# IF.net
KiCad netlist of a schematic drawn in Altium Designer
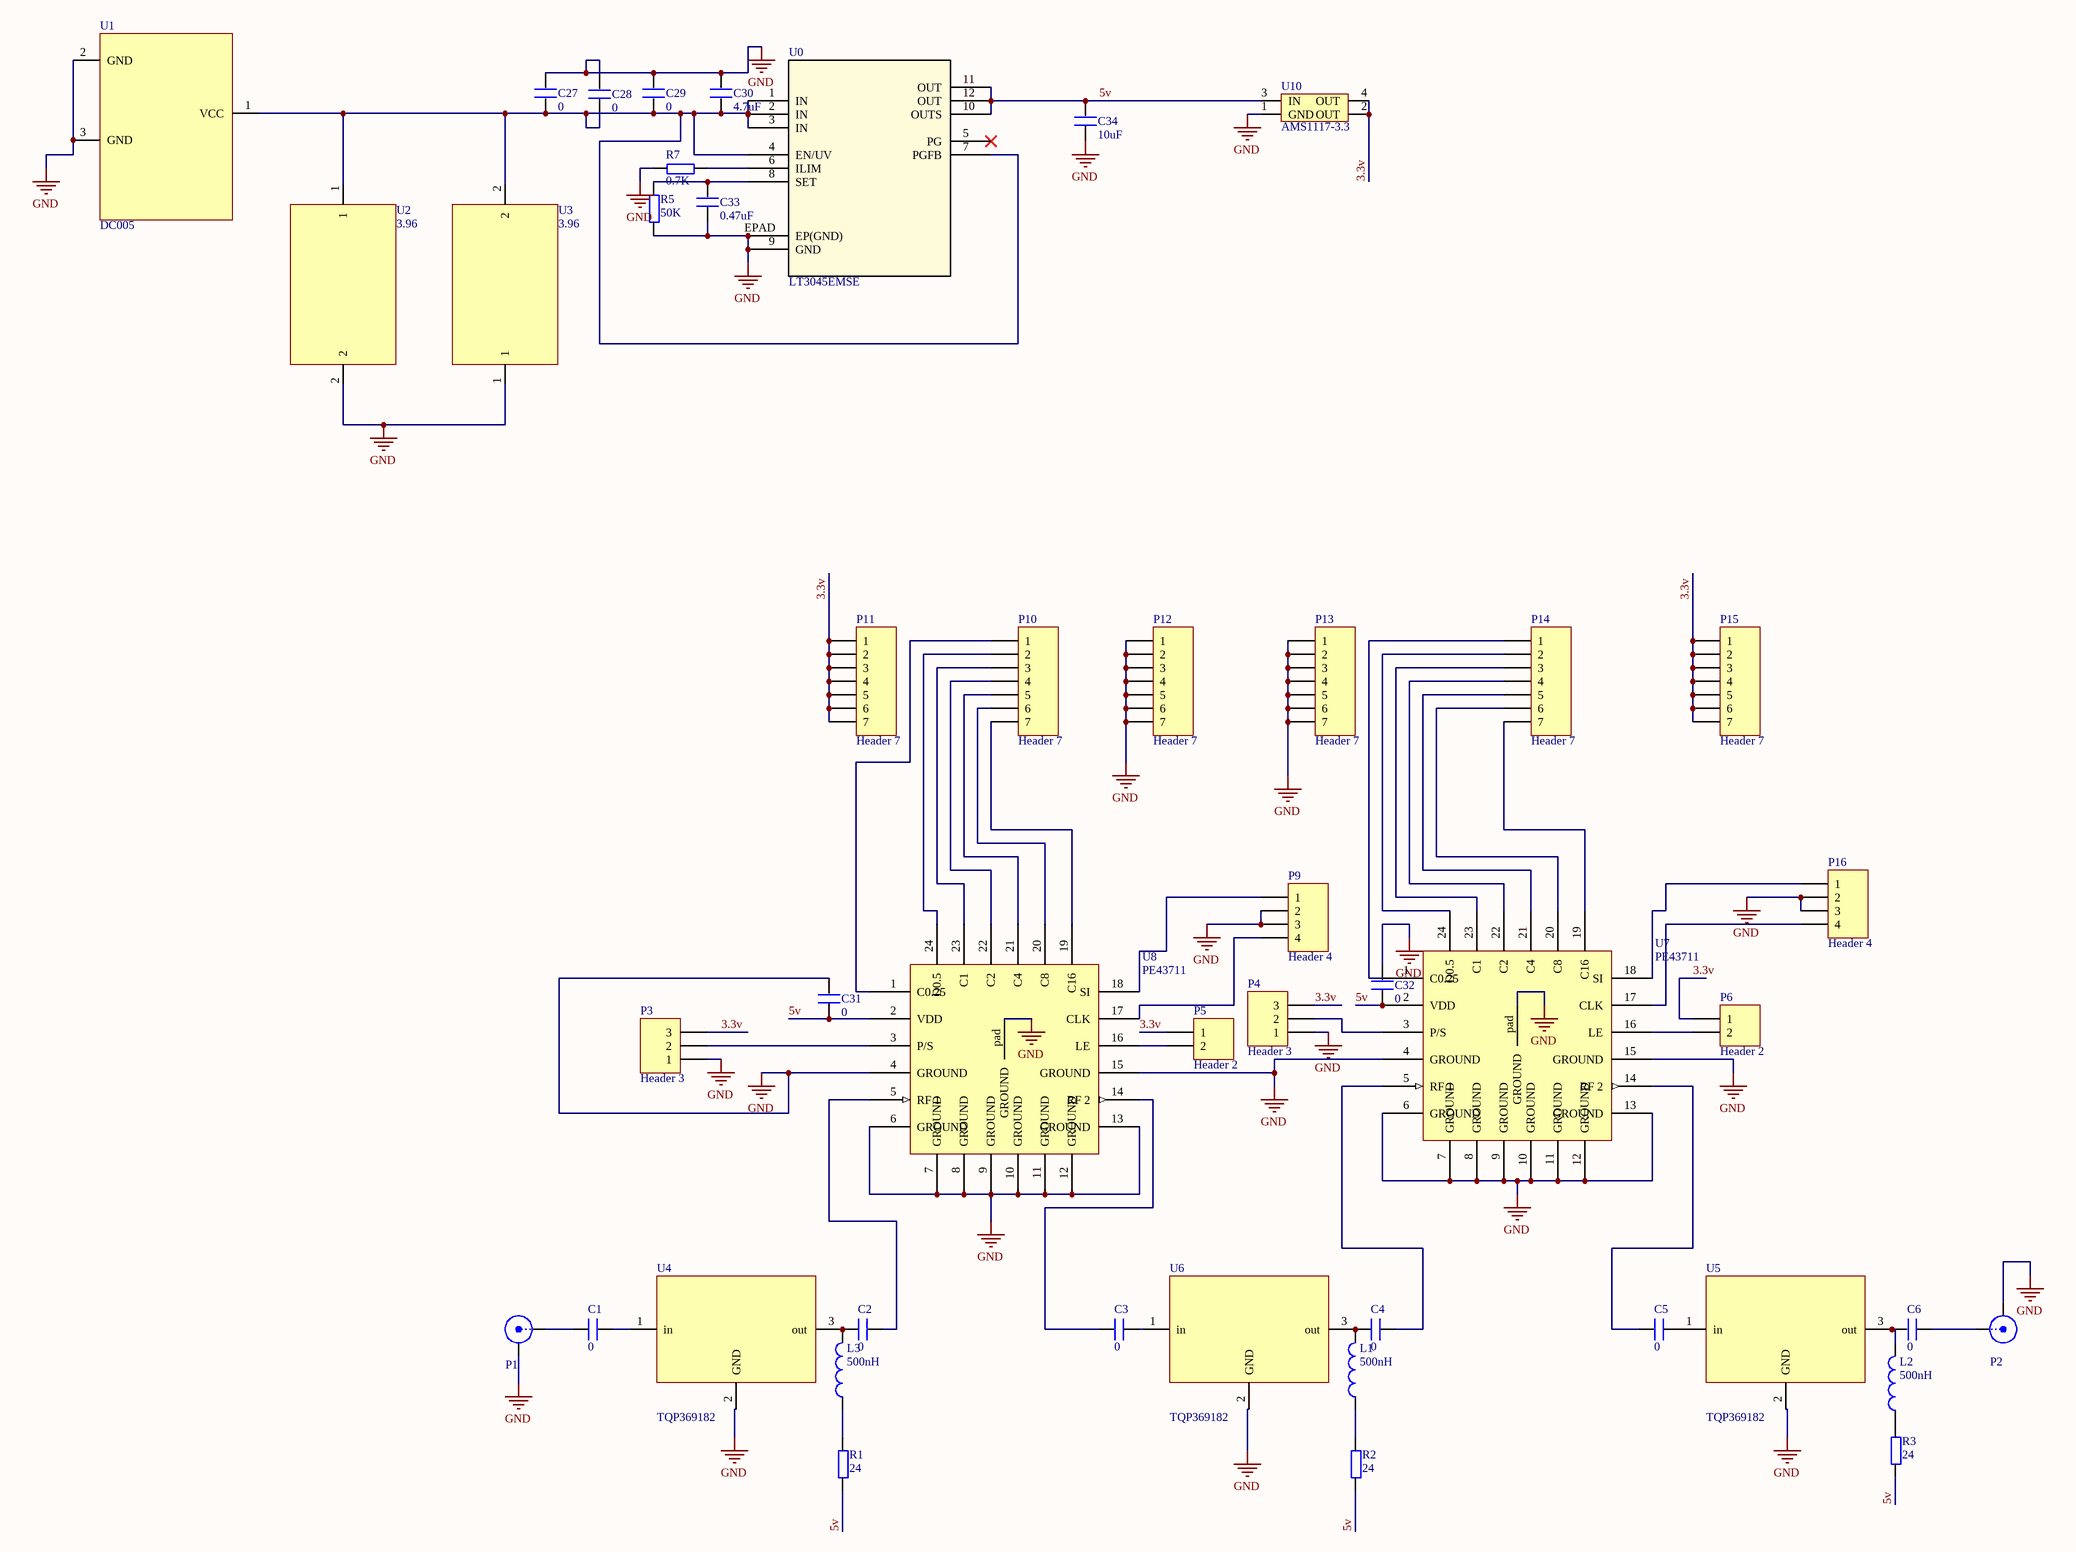
[diagram p0: IF.SchDoc]

(export (version "E")
  (design (tool "Eeschema 10.0.6"))
  (components
    (comp (ref "C1")
      (value "0")
      (footprint "0402")
      (description "Capacitor")
      (libsource (lib "MYLIB") (part "C"))
    )
    (comp (ref "C2")
      (value "0")
      (footprint "0402")
      (description "Capacitor")
      (libsource (lib "MYLIB") (part "C"))
    )
    (comp (ref "C3")
      (value "0")
      (footprint "0402")
      (description "Capacitor")
      (libsource (lib "MYLIB") (part "C"))
    )
    (comp (ref "C4")
      (value "0")
      (footprint "0402")
      (description "Capacitor")
      (libsource (lib "MYLIB") (part "C"))
    )
    (comp (ref "C5")
      (value "0")
      (footprint "0402")
      (description "Capacitor")
      (libsource (lib "MYLIB") (part "C"))
    )
    (comp (ref "C6")
      (value "0")
      (footprint "0402")
      (description "Capacitor")
      (libsource (lib "MYLIB") (part "C"))
    )
    (comp (ref "C27")
      (value "0")
      (footprint "CAP 1.5*4*8")
      (description "Capacitor")
      (libsource (lib "MYLIB") (part "C"))
    )
    (comp (ref "C28")
      (value "0")
      (footprint "CAP 1.5*4*8")
      (description "Capacitor")
      (libsource (lib "MYLIB") (part "C"))
    )
    (comp (ref "C29")
      (value "0")
      (footprint "0603C")
      (description "Capacitor")
      (libsource (lib "MYLIB") (part "C"))
    )
    (comp (ref "C30")
      (value "4.7uF")
      (footprint "0603C")
      (description "Capacitor")
      (libsource (lib "MYLIB") (part "C"))
    )
    (comp (ref "C31")
      (value "0")
      (footprint "0402")
      (description "Capacitor")
      (libsource (lib "MYLIB") (part "C"))
    )
    (comp (ref "C32")
      (value "0")
      (footprint "0402")
      (description "Capacitor")
      (libsource (lib "MYLIB") (part "C"))
    )
    (comp (ref "C33")
      (value "0.47uF")
      (footprint "0402")
      (description "Capacitor")
      (libsource (lib "MYLIB") (part "C"))
    )
    (comp (ref "C34")
      (value "10uF")
      (footprint "0402")
      (description "Capacitor")
      (libsource (lib "MYLIB") (part "C"))
    )
    (comp (ref "L1")
      (value "500nH")
      (footprint "0402")
      (description "Inductor")
      (fields (field (name "PUBLISHER") "Altium Limited"))
      (libsource (lib "MYLIB") (part "Inductor"))
    )
    (comp (ref "L2")
      (value "500nH")
      (footprint "0402")
      (description "Inductor")
      (fields (field (name "PUBLISHER") "Altium Limited"))
      (libsource (lib "MYLIB") (part "Inductor"))
    )
    (comp (ref "L3")
      (value "500nH")
      (footprint "0402")
      (description "Inductor")
      (fields (field (name "PUBLISHER") "Altium Limited"))
      (libsource (lib "MYLIB") (part "Inductor"))
    )
    (comp (ref "P1")
      (value "SMA")
      (footprint "SMA")
      (description "SMA Connector")
      (libsource (lib "MYLIB") (part "SMA"))
    )
    (comp (ref "P2")
      (value "SMA")
      (footprint "SMA")
      (description "SMA Connector")
      (libsource (lib "MYLIB") (part "SMA"))
    )
    (comp (ref "P3")
      (value "Header 3")
      (footprint "HDR1X3")
      (description "Header, 3-Pin")
      (fields (field (name "PUBLISHER") "Altium Limited"))
      (libsource (lib "Miscellaneous Connectors") (part "Header 3"))
    )
    (comp (ref "P4")
      (value "Header 3")
      (footprint "HDR1X3")
      (description "Header, 3-Pin")
      (fields (field (name "PUBLISHER") "Altium Limited"))
      (libsource (lib "Miscellaneous Connectors") (part "Header 3"))
    )
    (comp (ref "P5")
      (value "Header 2")
      (footprint "HDR1X2")
      (description "Header, 2-Pin")
      (fields (field (name "PUBLISHER") "Altium Limited"))
      (libsource (lib "Miscellaneous Connectors") (part "Header 2"))
    )
    (comp (ref "P6")
      (value "Header 2")
      (footprint "HDR1X2")
      (description "Header, 2-Pin")
      (fields (field (name "PUBLISHER") "Altium Limited"))
      (libsource (lib "Miscellaneous Connectors") (part "Header 2"))
    )
    (comp (ref "P9")
      (value "Header 4")
      (footprint "HDR1X4")
      (description "Header, 4-Pin")
      (fields (field (name "PUBLISHER") "Altium Limited"))
      (libsource (lib "Miscellaneous Connectors") (part "Header 4"))
    )
    (comp (ref "P10")
      (value "Header 7")
      (footprint "HDR1X7")
      (description "Header, 7-Pin")
      (fields (field (name "PUBLISHER") "Altium Limited"))
      (libsource (lib "Miscellaneous Connectors") (part "Header 7"))
    )
    (comp (ref "P11")
      (value "Header 7")
      (footprint "HDR1X7")
      (description "Header, 7-Pin")
      (fields (field (name "PUBLISHER") "Altium Limited"))
      (libsource (lib "Miscellaneous Connectors") (part "Header 7"))
    )
    (comp (ref "P12")
      (value "Header 7")
      (footprint "HDR1X7")
      (description "Header, 7-Pin")
      (fields (field (name "PUBLISHER") "Altium Limited"))
      (libsource (lib "Miscellaneous Connectors") (part "Header 7"))
    )
    (comp (ref "P13")
      (value "Header 7")
      (footprint "HDR1X7")
      (description "Header, 7-Pin")
      (fields (field (name "PUBLISHER") "Altium Limited"))
      (libsource (lib "Miscellaneous Connectors") (part "Header 7"))
    )
    (comp (ref "P14")
      (value "Header 7")
      (footprint "HDR1X7")
      (description "Header, 7-Pin")
      (fields (field (name "PUBLISHER") "Altium Limited"))
      (libsource (lib "Miscellaneous Connectors") (part "Header 7"))
    )
    (comp (ref "P15")
      (value "Header 7")
      (footprint "HDR1X7")
      (description "Header, 7-Pin")
      (fields (field (name "PUBLISHER") "Altium Limited"))
      (libsource (lib "Miscellaneous Connectors") (part "Header 7"))
    )
    (comp (ref "P16")
      (value "Header 4")
      (footprint "HDR1X4")
      (description "Header, 4-Pin")
      (fields (field (name "PUBLISHER") "Altium Limited"))
      (libsource (lib "Miscellaneous Connectors") (part "Header 4"))
    )
    (comp (ref "R1")
      (value "24")
      (footprint "0805")
      (description "Resistor")
      (libsource (lib "MYLIB") (part "Resistor"))
    )
    (comp (ref "R2")
      (value "24")
      (footprint "0805")
      (description "Resistor")
      (libsource (lib "MYLIB") (part "Resistor"))
    )
    (comp (ref "R3")
      (value "24")
      (footprint "0805")
      (description "Resistor")
      (libsource (lib "MYLIB") (part "Resistor"))
    )
    (comp (ref "R5")
      (value "50K")
      (footprint "0402")
      (description "Resistor")
      (libsource (lib "MYLIB") (part "Resistor"))
    )
    (comp (ref "R7")
      (value "0.7K")
      (footprint "0402")
      (description "Resistor")
      (libsource (lib "MYLIB") (part "Resistor"))
    )
    (comp (ref "U0")
      (value "LT3045EMSE")
      (footprint "MSOP12-MSE-RevG_ADI")
      (description "No Description Available")
      (fields (field (name "COPYRIGHT") "Copyright (C) 2018 Accelerated Designs. All rights reserved"))
      (libsource (lib "MYLIB") (part "LT3045EMSE"))
    )
    (comp (ref "U1") (value "DC005") (footprint "DC10B") (libsource (lib "MYLIB") (part "DC005")))
    (comp (ref "U2") (value "3.96") (footprint "3.96") (libsource (lib "MYLIB") (part "3.96")))
    (comp (ref "U3") (value "3.96") (footprint "3.96") (libsource (lib "") (part "3.96_1")))
    (comp (ref "U4") (value "TQP369182") (footprint "SOT89_M") (libsource (lib "MYLIB") (part "TQP369182")))
    (comp (ref "U5") (value "TQP369182") (footprint "SOT89_M") (libsource (lib "MYLIB") (part "TQP369182")))
    (comp (ref "U6") (value "TQP369182") (footprint "SOT89_M") (libsource (lib "MYLIB") (part "TQP369182")))
    (comp (ref "U7") (value "PE43711") (footprint "PE43711") (libsource (lib "MYLIB") (part "PE43711")))
    (comp (ref "U8") (value "PE43711") (footprint "PE43711") (libsource (lib "MYLIB") (part "PE43711")))
    (comp (ref "U10") (value "AMS1117-3.3") (footprint "AMS1117") (libsource (lib "MYLIB") (part "AMS1117")))
  )
  (nets
    (net (code "1") (name "/3.3v") (class "Default")
      (node (ref "P11") (pin "1") (pinfunction "1_1") (pintype "passive"))
      (node (ref "P11") (pin "2") (pinfunction "2_2") (pintype "passive"))
      (node (ref "P11") (pin "3") (pinfunction "3_3") (pintype "passive"))
      (node (ref "P11") (pin "4") (pinfunction "4_4") (pintype "passive"))
      (node (ref "P11") (pin "5") (pinfunction "5_5") (pintype "passive"))
      (node (ref "P11") (pin "6") (pinfunction "6_6") (pintype "passive"))
      (node (ref "P11") (pin "7") (pinfunction "7_7") (pintype "passive"))
      (node (ref "P15") (pin "1") (pinfunction "1_1") (pintype "passive"))
      (node (ref "P15") (pin "2") (pinfunction "2_2") (pintype "passive"))
      (node (ref "P15") (pin "3") (pinfunction "3_3") (pintype "passive"))
      (node (ref "P15") (pin "4") (pinfunction "4_4") (pintype "passive"))
      (node (ref "P15") (pin "5") (pinfunction "5_5") (pintype "passive"))
      (node (ref "P15") (pin "6") (pinfunction "6_6") (pintype "passive"))
      (node (ref "P15") (pin "7") (pinfunction "7_7") (pintype "passive"))
      (node (ref "P3") (pin "3") (pinfunction "3_3") (pintype "passive"))
      (node (ref "P4") (pin "3") (pinfunction "3_3") (pintype "passive"))
      (node (ref "P5") (pin "1") (pinfunction "1_1") (pintype "passive"))
      (node (ref "P6") (pin "1") (pinfunction "1_1") (pintype "passive"))
      (node (ref "U10") (pin "2") (pinfunction "OUT_2") (pintype "passive"))
      (node (ref "U10") (pin "4") (pinfunction "OUT_4") (pintype "passive"))
    )
    (net (code "2") (name "/5v") (class "Default")
      (node (ref "C31") (pin "1") (pintype "passive"))
      (node (ref "C32") (pin "1") (pintype "passive"))
      (node (ref "C34") (pin "2") (pintype "passive"))
      (node (ref "R1") (pin "1") (pintype "passive"))
      (node (ref "R2") (pin "1") (pintype "passive"))
      (node (ref "R3") (pin "1") (pintype "passive"))
      (node (ref "U0") (pin "10") (pinfunction "OUTS_10") (pintype "passive"))
      (node (ref "U0") (pin "11") (pinfunction "OUT_11") (pintype "passive"))
      (node (ref "U0") (pin "12") (pinfunction "OUT_12") (pintype "passive"))
      (node (ref "U10") (pin "3") (pinfunction "IN_3") (pintype "passive"))
      (node (ref "U7") (pin "2") (pinfunction "VDD_2") (pintype "power_in"))
      (node (ref "U8") (pin "2") (pinfunction "VDD_2") (pintype "power_in"))
    )
    (net (code "3") (name "GND") (class "Default")
      (node (ref "C27") (pin "2") (pintype "passive"))
      (node (ref "C28") (pin "2") (pintype "passive"))
      (node (ref "C29") (pin "2") (pintype "passive"))
      (node (ref "C30") (pin "2") (pintype "passive"))
      (node (ref "C31") (pin "2") (pintype "passive"))
      (node (ref "C32") (pin "2") (pintype "passive"))
      (node (ref "C33") (pin "1") (pintype "passive"))
      (node (ref "C34") (pin "1") (pintype "passive"))
      (node (ref "P1") (pin "2") (pinfunction "Y_2") (pintype "passive"))
      (node (ref "P12") (pin "1") (pinfunction "1_1") (pintype "passive"))
      (node (ref "P12") (pin "2") (pinfunction "2_2") (pintype "passive"))
      (node (ref "P12") (pin "3") (pinfunction "3_3") (pintype "passive"))
      (node (ref "P12") (pin "4") (pinfunction "4_4") (pintype "passive"))
      (node (ref "P12") (pin "5") (pinfunction "5_5") (pintype "passive"))
      (node (ref "P12") (pin "6") (pinfunction "6_6") (pintype "passive"))
      (node (ref "P12") (pin "7") (pinfunction "7_7") (pintype "passive"))
      (node (ref "P13") (pin "1") (pinfunction "1_1") (pintype "passive"))
      (node (ref "P13") (pin "2") (pinfunction "2_2") (pintype "passive"))
      (node (ref "P13") (pin "3") (pinfunction "3_3") (pintype "passive"))
      (node (ref "P13") (pin "4") (pinfunction "4_4") (pintype "passive"))
      (node (ref "P13") (pin "5") (pinfunction "5_5") (pintype "passive"))
      (node (ref "P13") (pin "6") (pinfunction "6_6") (pintype "passive"))
      (node (ref "P13") (pin "7") (pinfunction "7_7") (pintype "passive"))
      (node (ref "P16") (pin "2") (pinfunction "2_2") (pintype "passive"))
      (node (ref "P16") (pin "3") (pinfunction "3_3") (pintype "passive"))
      (node (ref "P2") (pin "2") (pinfunction "Y_2") (pintype "passive"))
      (node (ref "P3") (pin "1") (pinfunction "1_1") (pintype "passive"))
      (node (ref "P4") (pin "1") (pinfunction "1_1") (pintype "passive"))
      (node (ref "P9") (pin "2") (pinfunction "2_2") (pintype "passive"))
      (node (ref "P9") (pin "3") (pinfunction "3_3") (pintype "passive"))
      (node (ref "R5") (pin "1") (pintype "passive"))
      (node (ref "R7") (pin "1") (pintype "passive"))
      (node (ref "U0") (pin "9") (pinfunction "GND_9") (pintype "passive"))
      (node (ref "U0") (pin "EPAD") (pinfunction "EP(GND)_EPAD") (pintype "passive"))
      (node (ref "U1") (pin "2") (pinfunction "GND_2") (pintype "passive"))
      (node (ref "U1") (pin "3") (pinfunction "GND_3") (pintype "passive"))
      (node (ref "U10") (pin "1") (pinfunction "GND_1") (pintype "passive"))
      (node (ref "U2") (pin "2") (pinfunction "2_2") (pintype "passive"))
      (node (ref "U3") (pin "1") (pinfunction "1_1") (pintype "passive"))
      (node (ref "U4") (pin "2") (pinfunction "GND_2") (pintype "passive"))
      (node (ref "U5") (pin "2") (pinfunction "GND_2") (pintype "passive"))
      (node (ref "U6") (pin "2") (pinfunction "GND_2") (pintype "passive"))
      (node (ref "U7") (pin "10") (pinfunction "GROUND_10") (pintype "passive"))
      (node (ref "U7") (pin "11") (pinfunction "GROUND_11") (pintype "passive"))
      (node (ref "U7") (pin "12") (pinfunction "GROUND_12") (pintype "passive"))
      (node (ref "U7") (pin "13") (pinfunction "GROUND_13") (pintype "passive"))
      (node (ref "U7") (pin "15") (pinfunction "GROUND_15") (pintype "passive"))
      (node (ref "U7") (pin "4") (pinfunction "GROUND_4") (pintype "passive"))
      (node (ref "U7") (pin "6") (pinfunction "GROUND_6") (pintype "passive"))
      (node (ref "U7") (pin "7") (pinfunction "GROUND_7") (pintype "passive"))
      (node (ref "U7") (pin "8") (pinfunction "GROUND_8") (pintype "passive"))
      (node (ref "U7") (pin "9") (pinfunction "GROUND_9") (pintype "passive"))
      (node (ref "U7") (pin "pad") (pinfunction "GROUND_pad") (pintype "passive"))
      (node (ref "U8") (pin "10") (pinfunction "GROUND_10") (pintype "passive"))
      (node (ref "U8") (pin "11") (pinfunction "GROUND_11") (pintype "passive"))
      (node (ref "U8") (pin "12") (pinfunction "GROUND_12") (pintype "passive"))
      (node (ref "U8") (pin "13") (pinfunction "GROUND_13") (pintype "passive"))
      (node (ref "U8") (pin "15") (pinfunction "GROUND_15") (pintype "passive"))
      (node (ref "U8") (pin "4") (pinfunction "GROUND_4") (pintype "passive"))
      (node (ref "U8") (pin "6") (pinfunction "GROUND_6") (pintype "passive"))
      (node (ref "U8") (pin "7") (pinfunction "GROUND_7") (pintype "passive"))
      (node (ref "U8") (pin "8") (pinfunction "GROUND_8") (pintype "passive"))
      (node (ref "U8") (pin "9") (pinfunction "GROUND_9") (pintype "passive"))
      (node (ref "U8") (pin "pad") (pinfunction "GROUND_pad") (pintype "passive"))
    )
    (net (code "4") (name "Net-(L1-Pad1)") (class "Default")
      (node (ref "L1") (pin "1") (pinfunction "1_1") (pintype "passive"))
      (node (ref "R2") (pin "2") (pintype "passive"))
    )
    (net (code "5") (name "Net-(L2-Pad1)") (class "Default")
      (node (ref "L2") (pin "1") (pinfunction "1_1") (pintype "passive"))
      (node (ref "R3") (pin "2") (pintype "passive"))
    )
    (net (code "6") (name "Net-(L3-Pad1)") (class "Default")
      (node (ref "L3") (pin "1") (pinfunction "1_1") (pintype "passive"))
      (node (ref "R1") (pin "2") (pintype "passive"))
    )
    (net (code "7") (name "Net-(P1-X)") (class "Default")
      (node (ref "C1") (pin "1") (pintype "passive"))
      (node (ref "P1") (pin "1") (pinfunction "X_1") (pintype "passive"))
    )
    (net (code "8") (name "Net-(P2-X)") (class "Default")
      (node (ref "C6") (pin "2") (pintype "passive"))
      (node (ref "P2") (pin "1") (pinfunction "X_1") (pintype "passive"))
    )
    (net (code "9") (name "Net-(U0-EN{slash}UV)") (class "Default")
      (node (ref "C27") (pin "1") (pintype "passive"))
      (node (ref "C28") (pin "1") (pintype "passive"))
      (node (ref "C29") (pin "1") (pintype "passive"))
      (node (ref "C30") (pin "1") (pintype "passive"))
      (node (ref "U0") (pin "1") (pinfunction "IN_1") (pintype "passive"))
      (node (ref "U0") (pin "2") (pinfunction "IN_2") (pintype "passive"))
      (node (ref "U0") (pin "3") (pinfunction "IN_3") (pintype "passive"))
      (node (ref "U0") (pin "4") (pinfunction "EN/UV_4") (pintype "passive"))
      (node (ref "U0") (pin "7") (pinfunction "PGFB_7") (pintype "passive"))
      (node (ref "U1") (pin "1") (pinfunction "VCC_1") (pintype "passive"))
      (node (ref "U2") (pin "1") (pinfunction "1_1") (pintype "passive"))
      (node (ref "U3") (pin "2") (pinfunction "2_2") (pintype "passive"))
    )
    (net (code "10") (name "Net-(U0-ILIM)") (class "Default")
      (node (ref "R7") (pin "2") (pintype "passive"))
      (node (ref "U0") (pin "6") (pinfunction "ILIM_6") (pintype "passive"))
    )
    (net (code "11") (name "Net-(U0-SET)") (class "Default")
      (node (ref "C33") (pin "2") (pintype "passive"))
      (node (ref "R5") (pin "2") (pintype "passive"))
      (node (ref "U0") (pin "8") (pinfunction "SET_8") (pintype "passive"))
    )
    (net (code "12") (name "Net-(U4-in)") (class "Default")
      (node (ref "C1") (pin "2") (pintype "passive"))
      (node (ref "U4") (pin "1") (pinfunction "in_1") (pintype "passive"))
    )
    (net (code "13") (name "Net-(U4-out)") (class "Default")
      (node (ref "C2") (pin "1") (pintype "passive"))
      (node (ref "L3") (pin "2") (pinfunction "2_2") (pintype "passive"))
      (node (ref "U4") (pin "3") (pinfunction "out_3") (pintype "passive"))
    )
    (net (code "14") (name "Net-(U5-in)") (class "Default")
      (node (ref "C5") (pin "2") (pintype "passive"))
      (node (ref "U5") (pin "1") (pinfunction "in_1") (pintype "passive"))
    )
    (net (code "15") (name "Net-(U5-out)") (class "Default")
      (node (ref "C6") (pin "1") (pintype "passive"))
      (node (ref "L2") (pin "2") (pinfunction "2_2") (pintype "passive"))
      (node (ref "U5") (pin "3") (pinfunction "out_3") (pintype "passive"))
    )
    (net (code "16") (name "Net-(U6-in)") (class "Default")
      (node (ref "C3") (pin "2") (pintype "passive"))
      (node (ref "U6") (pin "1") (pinfunction "in_1") (pintype "passive"))
    )
    (net (code "17") (name "Net-(U6-out)") (class "Default")
      (node (ref "C4") (pin "1") (pintype "passive"))
      (node (ref "L1") (pin "2") (pinfunction "2_2") (pintype "passive"))
      (node (ref "U6") (pin "3") (pinfunction "out_3") (pintype "passive"))
    )
    (net (code "18") (name "Net-(U7-C0.25)") (class "Default")
      (node (ref "P14") (pin "1") (pinfunction "1_1") (pintype "passive"))
      (node (ref "U7") (pin "1") (pinfunction "C0.25_1") (pintype "open_collector"))
    )
    (net (code "19") (name "Net-(U7-C1)") (class "Default")
      (node (ref "P14") (pin "3") (pinfunction "3_3") (pintype "passive"))
      (node (ref "U7") (pin "23") (pinfunction "C1_23") (pintype "passive"))
    )
    (net (code "20") (name "Net-(U7-C2)") (class "Default")
      (node (ref "P14") (pin "4") (pinfunction "4_4") (pintype "passive"))
      (node (ref "U7") (pin "22") (pinfunction "C2_22") (pintype "passive"))
    )
    (net (code "21") (name "Net-(U7-C4)") (class "Default")
      (node (ref "P14") (pin "5") (pinfunction "5_5") (pintype "passive"))
      (node (ref "U7") (pin "21") (pinfunction "C4_21") (pintype "passive"))
    )
    (net (code "22") (name "Net-(U7-C8)") (class "Default")
      (node (ref "P14") (pin "6") (pinfunction "6_6") (pintype "passive"))
      (node (ref "U7") (pin "20") (pinfunction "C8_20") (pintype "passive"))
    )
    (net (code "23") (name "Net-(U7-C16)") (class "Default")
      (node (ref "P14") (pin "7") (pinfunction "7_7") (pintype "passive"))
      (node (ref "U7") (pin "19") (pinfunction "C16_19") (pintype "open_collector"))
    )
    (net (code "24") (name "Net-(U7-CLK)") (class "Default")
      (node (ref "P16") (pin "4") (pinfunction "4_4") (pintype "passive"))
      (node (ref "U7") (pin "17") (pinfunction "CLK_17") (pintype "passive"))
    )
    (net (code "25") (name "Net-(U7-D0.5)") (class "Default")
      (node (ref "P14") (pin "2") (pinfunction "2_2") (pintype "passive"))
      (node (ref "U7") (pin "24") (pinfunction "D0.5_24") (pintype "passive"))
    )
    (net (code "26") (name "Net-(U7-LE)") (class "Default")
      (node (ref "P6") (pin "2") (pinfunction "2_2") (pintype "passive"))
      (node (ref "U7") (pin "16") (pinfunction "LE_16") (pintype "passive"))
    )
    (net (code "27") (name "Net-(U7-P{slash}S)") (class "Default")
      (node (ref "P4") (pin "2") (pinfunction "2_2") (pintype "passive"))
      (node (ref "U7") (pin "3") (pinfunction "P/S_3") (pintype "passive"))
    )
    (net (code "28") (name "Net-(U7-RF_1)") (class "Default")
      (node (ref "C4") (pin "2") (pintype "passive"))
      (node (ref "U7") (pin "5") (pinfunction "RF_1_5") (pintype "input"))
    )
    (net (code "29") (name "Net-(U7-RF_2)") (class "Default")
      (node (ref "C5") (pin "1") (pintype "passive"))
      (node (ref "U7") (pin "14") (pinfunction "RF_2_14") (pintype "output"))
    )
    (net (code "30") (name "Net-(U7-SI)") (class "Default")
      (node (ref "P16") (pin "1") (pinfunction "1_1") (pintype "passive"))
      (node (ref "U7") (pin "18") (pinfunction "SI_18") (pintype "passive"))
    )
    (net (code "31") (name "Net-(U8-C0.25)") (class "Default")
      (node (ref "P10") (pin "1") (pinfunction "1_1") (pintype "passive"))
      (node (ref "U8") (pin "1") (pinfunction "C0.25_1") (pintype "open_collector"))
    )
    (net (code "32") (name "Net-(U8-C1)") (class "Default")
      (node (ref "P10") (pin "3") (pinfunction "3_3") (pintype "passive"))
      (node (ref "U8") (pin "23") (pinfunction "C1_23") (pintype "passive"))
    )
    (net (code "33") (name "Net-(U8-C2)") (class "Default")
      (node (ref "P10") (pin "4") (pinfunction "4_4") (pintype "passive"))
      (node (ref "U8") (pin "22") (pinfunction "C2_22") (pintype "passive"))
    )
    (net (code "34") (name "Net-(U8-C4)") (class "Default")
      (node (ref "P10") (pin "5") (pinfunction "5_5") (pintype "passive"))
      (node (ref "U8") (pin "21") (pinfunction "C4_21") (pintype "passive"))
    )
    (net (code "35") (name "Net-(U8-C8)") (class "Default")
      (node (ref "P10") (pin "6") (pinfunction "6_6") (pintype "passive"))
      (node (ref "U8") (pin "20") (pinfunction "C8_20") (pintype "passive"))
    )
    (net (code "36") (name "Net-(U8-C16)") (class "Default")
      (node (ref "P10") (pin "7") (pinfunction "7_7") (pintype "passive"))
      (node (ref "U8") (pin "19") (pinfunction "C16_19") (pintype "open_collector"))
    )
    (net (code "37") (name "Net-(U8-CLK)") (class "Default")
      (node (ref "P9") (pin "4") (pinfunction "4_4") (pintype "passive"))
      (node (ref "U8") (pin "17") (pinfunction "CLK_17") (pintype "passive"))
    )
    (net (code "38") (name "Net-(U8-D0.5)") (class "Default")
      (node (ref "P10") (pin "2") (pinfunction "2_2") (pintype "passive"))
      (node (ref "U8") (pin "24") (pinfunction "D0.5_24") (pintype "passive"))
    )
    (net (code "39") (name "Net-(U8-LE)") (class "Default")
      (node (ref "P5") (pin "2") (pinfunction "2_2") (pintype "passive"))
      (node (ref "U8") (pin "16") (pinfunction "LE_16") (pintype "passive"))
    )
    (net (code "40") (name "Net-(U8-P{slash}S)") (class "Default")
      (node (ref "P3") (pin "2") (pinfunction "2_2") (pintype "passive"))
      (node (ref "U8") (pin "3") (pinfunction "P/S_3") (pintype "passive"))
    )
    (net (code "41") (name "Net-(U8-RF_1)") (class "Default")
      (node (ref "C2") (pin "2") (pintype "passive"))
      (node (ref "U8") (pin "5") (pinfunction "RF_1_5") (pintype "input"))
    )
    (net (code "42") (name "Net-(U8-RF_2)") (class "Default")
      (node (ref "C3") (pin "1") (pintype "passive"))
      (node (ref "U8") (pin "14") (pinfunction "RF_2_14") (pintype "output"))
    )
    (net (code "43") (name "Net-(U8-SI)") (class "Default")
      (node (ref "P9") (pin "1") (pinfunction "1_1") (pintype "passive"))
      (node (ref "U8") (pin "18") (pinfunction "SI_18") (pintype "passive"))
    )
    (net (code "44") (name "unconnected-(U0-PG-Pad5)") (class "Default")
      (node (ref "U0") (pin "5") (pinfunction "PG_5") (pintype "passive+no_connect"))
    )
  )
)
